# Sheet2.net
KiCad netlist of a schematic drawn in Altium Designer
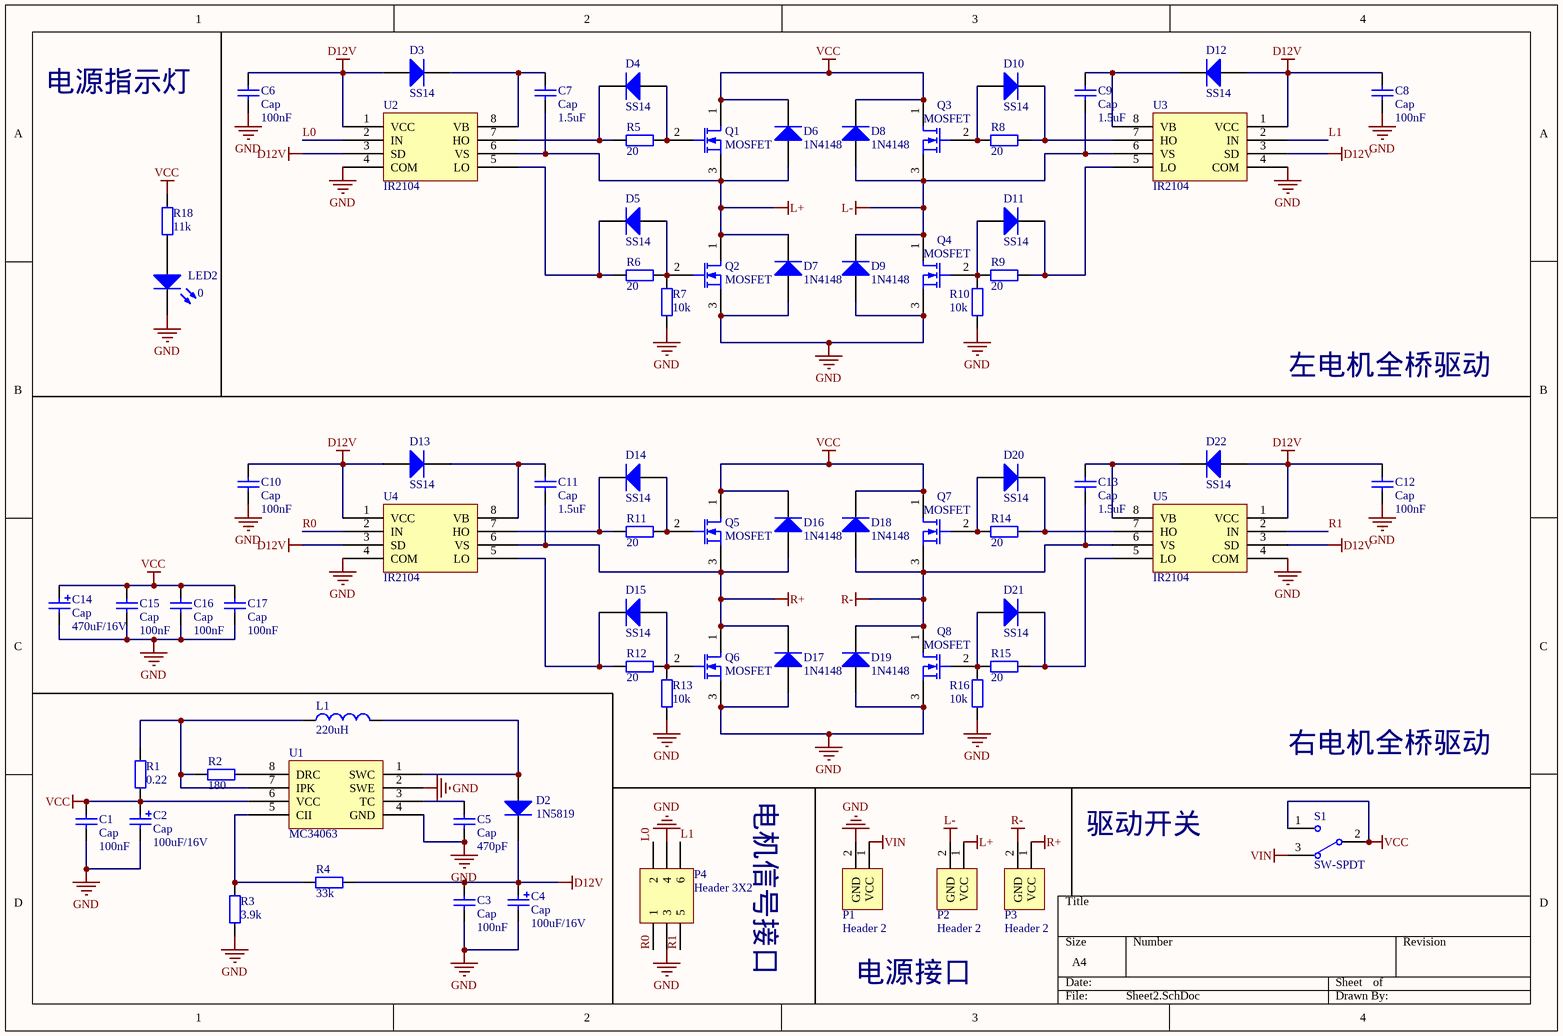
[diagram p0: Sheet2.SchDoc]

(export (version "E")
  (design (tool "Eeschema 10.0.6"))
  (components
    (comp (ref "C1")
      (value "Cap")
      (footprint "0603C")
      (description "Capacitor")
      (fields (field (name "ALTIUM_VALUE") "100nF") (field (name "PUBLISHER") "Altium Limited"))
      (libsource (lib "Schlib1") (part "Cap"))
    )
    (comp (ref "C2")
      (value "Cap")
      (footprint "电解电容")
      (description "Capacitor")
      (fields (field (name "ALTIUM_VALUE") "100uF/16V") (field (name "PUBLISHER") "Altium Limited"))
      (libsource (lib "Schlib1") (part "Cap2"))
    )
    (comp (ref "C3")
      (value "Cap")
      (footprint "0603C")
      (description "Capacitor")
      (fields (field (name "ALTIUM_VALUE") "100nF") (field (name "PUBLISHER") "Altium Limited"))
      (libsource (lib "Schlib1") (part "Cap"))
    )
    (comp (ref "C4")
      (value "Cap")
      (footprint "电解电容")
      (description "Capacitor")
      (fields (field (name "ALTIUM_VALUE") "100uF/16V") (field (name "PUBLISHER") "Altium Limited"))
      (libsource (lib "Schlib1") (part "Cap2"))
    )
    (comp (ref "C5")
      (value "Cap")
      (footprint "0603C")
      (description "Capacitor")
      (fields (field (name "ALTIUM_VALUE") "470pF") (field (name "PUBLISHER") "Altium Limited"))
      (libsource (lib "Schlib1") (part "Cap"))
    )
    (comp (ref "C6")
      (value "Cap")
      (footprint "0603C")
      (description "Capacitor")
      (fields (field (name "ALTIUM_VALUE") "100nF") (field (name "PUBLISHER") "Altium Limited"))
      (libsource (lib "Schlib1") (part "Cap"))
    )
    (comp (ref "C7")
      (value "Cap")
      (footprint "0603C")
      (description "Capacitor")
      (fields (field (name "ALTIUM_VALUE") "1.5uF") (field (name "PUBLISHER") "Altium Limited"))
      (libsource (lib "Schlib1") (part "Cap"))
    )
    (comp (ref "C8")
      (value "Cap")
      (footprint "0603C")
      (description "Capacitor")
      (fields (field (name "ALTIUM_VALUE") "100nF") (field (name "PUBLISHER") "Altium Limited"))
      (libsource (lib "Schlib1") (part "Cap"))
    )
    (comp (ref "C9")
      (value "Cap")
      (footprint "0603C")
      (description "Capacitor")
      (fields (field (name "ALTIUM_VALUE") "1.5uF") (field (name "PUBLISHER") "Altium Limited"))
      (libsource (lib "Schlib1") (part "Cap"))
    )
    (comp (ref "C10")
      (value "Cap")
      (footprint "0603C")
      (description "Capacitor")
      (fields (field (name "ALTIUM_VALUE") "100nF") (field (name "PUBLISHER") "Altium Limited"))
      (libsource (lib "Schlib1") (part "Cap"))
    )
    (comp (ref "C11")
      (value "Cap")
      (footprint "0603C")
      (description "Capacitor")
      (fields (field (name "ALTIUM_VALUE") "1.5uF") (field (name "PUBLISHER") "Altium Limited"))
      (libsource (lib "Schlib1") (part "Cap"))
    )
    (comp (ref "C12")
      (value "Cap")
      (footprint "0603C")
      (description "Capacitor")
      (fields (field (name "ALTIUM_VALUE") "100nF") (field (name "PUBLISHER") "Altium Limited"))
      (libsource (lib "Schlib1") (part "Cap"))
    )
    (comp (ref "C13")
      (value "Cap")
      (footprint "0603C")
      (description "Capacitor")
      (fields (field (name "ALTIUM_VALUE") "1.5uF") (field (name "PUBLISHER") "Altium Limited"))
      (libsource (lib "Schlib1") (part "Cap"))
    )
    (comp (ref "C14")
      (value "Cap")
      (footprint "CAP5.08/8")
      (description "Capacitor")
      (fields (field (name "ALTIUM_VALUE") "470uF/16V") (field (name "PUBLISHER") "Altium Limited"))
      (libsource (lib "Schlib1") (part "Cap2"))
    )
    (comp (ref "C15")
      (value "Cap")
      (footprint "0603C")
      (description "Capacitor")
      (fields (field (name "ALTIUM_VALUE") "100nF") (field (name "PUBLISHER") "Altium Limited"))
      (libsource (lib "Schlib1") (part "Cap"))
    )
    (comp (ref "C16")
      (value "Cap")
      (footprint "0603C")
      (description "Capacitor")
      (fields (field (name "ALTIUM_VALUE") "100nF") (field (name "PUBLISHER") "Altium Limited"))
      (libsource (lib "Schlib1") (part "Cap"))
    )
    (comp (ref "C17")
      (value "Cap")
      (footprint "0603C")
      (description "Capacitor")
      (fields (field (name "ALTIUM_VALUE") "100nF") (field (name "PUBLISHER") "Altium Limited"))
      (libsource (lib "Schlib1") (part "Cap"))
    )
    (comp (ref "D2")
      (value "1N5819")
      (footprint "ss54")
      (description "Default Diode")
      (fields (field (name "PUBLISHER") "Altium Limited"))
      (libsource (lib "Schlib1") (part "Diode_1"))
    )
    (comp (ref "D3")
      (value "SS14")
      (footprint "ss54")
      (description "Default Diode")
      (fields (field (name "PUBLISHER") "Altium Limited"))
      (libsource (lib "Schlib1") (part "Diode_1"))
    )
    (comp (ref "D4")
      (value "SS14")
      (footprint "ss54")
      (description "Default Diode")
      (fields (field (name "PUBLISHER") "Altium Limited"))
      (libsource (lib "Schlib1") (part "Diode_1"))
    )
    (comp (ref "D5")
      (value "SS14")
      (footprint "ss54")
      (description "Default Diode")
      (fields (field (name "PUBLISHER") "Altium Limited"))
      (libsource (lib "Schlib1") (part "Diode_1"))
    )
    (comp (ref "D6")
      (value "1N4148")
      (footprint "SOD123")
      (description "Default Diode")
      (fields (field (name "PUBLISHER") "Altium Limited"))
      (libsource (lib "Schlib1") (part "Diode_2"))
    )
    (comp (ref "D7")
      (value "1N4148")
      (footprint "SOD123")
      (description "Default Diode")
      (fields (field (name "PUBLISHER") "Altium Limited"))
      (libsource (lib "Schlib1") (part "Diode_2"))
    )
    (comp (ref "D8")
      (value "1N4148")
      (footprint "SOD123")
      (description "Default Diode")
      (fields (field (name "PUBLISHER") "Altium Limited"))
      (libsource (lib "Schlib1") (part "Diode_2"))
    )
    (comp (ref "D9")
      (value "1N4148")
      (footprint "SOD123")
      (description "Default Diode")
      (fields (field (name "PUBLISHER") "Altium Limited"))
      (libsource (lib "Schlib1") (part "Diode_2"))
    )
    (comp (ref "D10")
      (value "SS14")
      (footprint "ss54")
      (description "Default Diode")
      (fields (field (name "PUBLISHER") "Altium Limited"))
      (libsource (lib "Schlib1") (part "Diode_1"))
    )
    (comp (ref "D11")
      (value "SS14")
      (footprint "ss54")
      (description "Default Diode")
      (fields (field (name "PUBLISHER") "Altium Limited"))
      (libsource (lib "Schlib1") (part "Diode_1"))
    )
    (comp (ref "D12")
      (value "SS14")
      (footprint "ss54")
      (description "Default Diode")
      (fields (field (name "PUBLISHER") "Altium Limited"))
      (libsource (lib "Schlib1") (part "Diode_1"))
    )
    (comp (ref "D13")
      (value "SS14")
      (footprint "ss54")
      (description "Default Diode")
      (fields (field (name "PUBLISHER") "Altium Limited"))
      (libsource (lib "Schlib1") (part "Diode_1"))
    )
    (comp (ref "D14")
      (value "SS14")
      (footprint "ss54")
      (description "Default Diode")
      (fields (field (name "PUBLISHER") "Altium Limited"))
      (libsource (lib "Schlib1") (part "Diode_1"))
    )
    (comp (ref "D15")
      (value "SS14")
      (footprint "ss54")
      (description "Default Diode")
      (fields (field (name "PUBLISHER") "Altium Limited"))
      (libsource (lib "Schlib1") (part "Diode_1"))
    )
    (comp (ref "D16")
      (value "1N4148")
      (footprint "SOD123")
      (description "Default Diode")
      (fields (field (name "PUBLISHER") "Altium Limited"))
      (libsource (lib "Schlib1") (part "Diode_2"))
    )
    (comp (ref "D17")
      (value "1N4148")
      (footprint "SOD123")
      (description "Default Diode")
      (fields (field (name "PUBLISHER") "Altium Limited"))
      (libsource (lib "Schlib1") (part "Diode_2"))
    )
    (comp (ref "D18")
      (value "1N4148")
      (footprint "SOD123")
      (description "Default Diode")
      (fields (field (name "PUBLISHER") "Altium Limited"))
      (libsource (lib "Schlib1") (part "Diode_2"))
    )
    (comp (ref "D19")
      (value "1N4148")
      (footprint "SOD123")
      (description "Default Diode")
      (fields (field (name "PUBLISHER") "Altium Limited"))
      (libsource (lib "Schlib1") (part "Diode_2"))
    )
    (comp (ref "D20")
      (value "SS14")
      (footprint "ss54")
      (description "Default Diode")
      (fields (field (name "PUBLISHER") "Altium Limited"))
      (libsource (lib "Schlib1") (part "Diode_1"))
    )
    (comp (ref "D21")
      (value "SS14")
      (footprint "ss54")
      (description "Default Diode")
      (fields (field (name "PUBLISHER") "Altium Limited"))
      (libsource (lib "Schlib1") (part "Diode_1"))
    )
    (comp (ref "D22")
      (value "SS14")
      (footprint "ss54")
      (description "Default Diode")
      (fields (field (name "PUBLISHER") "Altium Limited"))
      (libsource (lib "Schlib1") (part "Diode_1"))
    )
    (comp (ref "L1")
      (value "220uH")
      (footprint "cd54")
      (description "Inductor")
      (fields (field (name "PUBLISHER") "Altium Limited"))
      (libsource (lib "Schlib1") (part "Inductor_2"))
    )
    (comp (ref "LED2")
      (value "0")
      (footprint "0603C")
      (description "Typical RED, GREEN, YELLOW, AMBER GaAs LED")
      (fields (field (name "PUBLISHER") "Altium Limited"))
      (libsource (lib "Schlib1") (part "LED2"))
    )
    (comp (ref "P1")
      (value "Header 2")
      (footprint "VCCBAT")
      (description "Header, 2-Pin")
      (fields (field (name "PUBLISHER") "Altium Limited"))
      (libsource (lib "Schlib1") (part "Header 2_2"))
    )
    (comp (ref "P2")
      (value "Header 2")
      (footprint "VCCBAT")
      (description "Header, 2-Pin")
      (fields (field (name "PUBLISHER") "Altium Limited"))
      (libsource (lib "Schlib1") (part "Header 2_2"))
    )
    (comp (ref "P3")
      (value "Header 2")
      (footprint "VCCBAT")
      (description "Header, 2-Pin")
      (fields (field (name "PUBLISHER") "Altium Limited"))
      (libsource (lib "Schlib1") (part "Header 2_2"))
    )
    (comp (ref "P4")
      (value "Header 3X2")
      (footprint "HDR2X3")
      (description "Header, 3-Pin, Dual row")
      (fields (field (name "PUBLISHER") "Altium Limited"))
      (libsource (lib "Miscellaneous Connectors") (part "Header 3X2"))
    )
    (comp (ref "Q1") (value "MOSFET") (footprint "DPAK-1") (libsource (lib "Schlib1") (part "MOSFET-N")))
    (comp (ref "Q2") (value "MOSFET") (footprint "DPAK-1") (libsource (lib "Schlib1") (part "MOSFET-N")))
    (comp (ref "Q3") (value "MOSFET") (footprint "DPAK-1") (libsource (lib "Schlib1") (part "MOSFET-N")))
    (comp (ref "Q4") (value "MOSFET") (footprint "DPAK-1") (libsource (lib "Schlib1") (part "MOSFET-N")))
    (comp (ref "Q5") (value "MOSFET") (footprint "DPAK-1") (libsource (lib "Schlib1") (part "MOSFET-N")))
    (comp (ref "Q6") (value "MOSFET") (footprint "DPAK-1") (libsource (lib "Schlib1") (part "MOSFET-N")))
    (comp (ref "Q7") (value "MOSFET") (footprint "DPAK-1") (libsource (lib "Schlib1") (part "MOSFET-N")))
    (comp (ref "Q8") (value "MOSFET") (footprint "DPAK-1") (libsource (lib "Schlib1") (part "MOSFET-N")))
    (comp (ref "R1")
      (value "0.22")
      (footprint "0603R")
      (description "Resistor")
      (fields (field (name "Comment") "Res2") (field (name "PUBLISHER") "Altium Limited"))
      (libsource (lib "") (part "Res2_1"))
    )
    (comp (ref "R2")
      (value "180")
      (footprint "0603R")
      (description "Resistor")
      (fields (field (name "Comment") "Res2") (field (name "PUBLISHER") "Altium Limited"))
      (libsource (lib "") (part "Res2_2"))
    )
    (comp (ref "R3")
      (value "3.9k")
      (footprint "0603R")
      (description "Resistor")
      (fields (field (name "Comment") "Res2") (field (name "PUBLISHER") "Altium Limited"))
      (libsource (lib "Schlib1") (part "Res2"))
    )
    (comp (ref "R4")
      (value "33k")
      (footprint "0603R")
      (description "Resistor")
      (fields (field (name "Comment") "Res2") (field (name "PUBLISHER") "Altium Limited"))
      (libsource (lib "") (part "Res2_2"))
    )
    (comp (ref "R5")
      (value "20")
      (footprint "0603R")
      (description "Resistor 用了15欧")
      (fields (field (name "Comment") "Res2") (field (name "PUBLISHER") "Altium Limited"))
      (libsource (lib "") (part "Res2_2"))
    )
    (comp (ref "R6")
      (value "20")
      (footprint "0603R")
      (description "Resistor")
      (fields (field (name "Comment") "Res2") (field (name "PUBLISHER") "Altium Limited"))
      (libsource (lib "") (part "Res2_2"))
    )
    (comp (ref "R7")
      (value "10k")
      (footprint "0603R")
      (description "Resistor")
      (fields (field (name "Comment") "Res2") (field (name "PUBLISHER") "Altium Limited"))
      (libsource (lib "") (part "Res2_1"))
    )
    (comp (ref "R8")
      (value "20")
      (footprint "0603R")
      (description "Resistor")
      (fields (field (name "Comment") "Res2") (field (name "PUBLISHER") "Altium Limited"))
      (libsource (lib "") (part "Res2_1"))
    )
    (comp (ref "R9")
      (value "20")
      (footprint "0603R")
      (description "Resistor")
      (fields (field (name "Comment") "Res2") (field (name "PUBLISHER") "Altium Limited"))
      (libsource (lib "") (part "Res2_1"))
    )
    (comp (ref "R10")
      (value "10k")
      (footprint "0603R")
      (description "Resistor")
      (fields (field (name "Comment") "Res2") (field (name "PUBLISHER") "Altium Limited"))
      (libsource (lib "") (part "Res2_3"))
    )
    (comp (ref "R11")
      (value "20")
      (footprint "0603R")
      (description "Resistor")
      (fields (field (name "Comment") "Res2") (field (name "PUBLISHER") "Altium Limited"))
      (libsource (lib "") (part "Res2_2"))
    )
    (comp (ref "R12")
      (value "20")
      (footprint "0603R")
      (description "Resistor")
      (fields (field (name "Comment") "Res2") (field (name "PUBLISHER") "Altium Limited"))
      (libsource (lib "") (part "Res2_2"))
    )
    (comp (ref "R13")
      (value "10k")
      (footprint "0603R")
      (description "Resistor")
      (fields (field (name "Comment") "Res2") (field (name "PUBLISHER") "Altium Limited"))
      (libsource (lib "") (part "Res2_1"))
    )
    (comp (ref "R14")
      (value "20")
      (footprint "0603R")
      (description "Resistor")
      (fields (field (name "Comment") "Res2") (field (name "PUBLISHER") "Altium Limited"))
      (libsource (lib "") (part "Res2_1"))
    )
    (comp (ref "R15")
      (value "20")
      (footprint "0603R")
      (description "Resistor")
      (fields (field (name "Comment") "Res2") (field (name "PUBLISHER") "Altium Limited"))
      (libsource (lib "") (part "Res2_1"))
    )
    (comp (ref "R16")
      (value "10k")
      (footprint "0603R")
      (description "Resistor")
      (fields (field (name "Comment") "Res2") (field (name "PUBLISHER") "Altium Limited"))
      (libsource (lib "") (part "Res2_3"))
    )
    (comp (ref "R18")
      (value "11k")
      (footprint "0603R")
      (description "Resistor")
      (fields (field (name "Comment") "Res2") (field (name "PUBLISHER") "Altium Limited"))
      (libsource (lib "") (part "Res2_1"))
    )
    (comp (ref "S1")
      (value "SW-SPDT")
      (footprint "SW")
      (description "SPDT Subminiature Toggle Switch, Right Angle Mounting, Vertical Actuation")
      (fields (field (name "PUBLISHER") "Altium Limited"))
      (libsource (lib "Miscellaneous Devices") (part "SW-SPDT"))
    )
    (comp (ref "U1") (value "MC34063") (footprint "SOIC-8") (libsource (lib "Schlib1") (part "MC34063")))
    (comp (ref "U2") (value "IR2104") (footprint "SOIC-8") (libsource (lib "") (part "IR2104_1")))
    (comp (ref "U3") (value "IR2104") (footprint "SOIC-8") (libsource (lib "Schlib1") (part "IR2104")))
    (comp (ref "U4") (value "IR2104") (footprint "SOIC-8") (libsource (lib "") (part "IR2104_1")))
    (comp (ref "U5") (value "IR2104") (footprint "SOIC-8") (libsource (lib "Schlib1") (part "IR2104")))
  )
  (nets
    (net (code "1") (name "/L0") (class "Default")
      (node (ref "P4") (pin "2") (pinfunction "2_2") (pintype "passive"))
      (node (ref "U2") (pin "2") (pinfunction "IN_2") (pintype "passive"))
    )
    (net (code "2") (name "/L1") (class "Default")
      (node (ref "P4") (pin "6") (pinfunction "6_6") (pintype "passive"))
      (node (ref "U3") (pin "2") (pinfunction "IN_2") (pintype "passive"))
    )
    (net (code "3") (name "/R0") (class "Default")
      (node (ref "P4") (pin "1") (pinfunction "1_1") (pintype "passive"))
      (node (ref "U4") (pin "2") (pinfunction "IN_2") (pintype "passive"))
    )
    (net (code "4") (name "/R1") (class "Default")
      (node (ref "P4") (pin "5") (pinfunction "5_5") (pintype "passive"))
      (node (ref "U5") (pin "2") (pinfunction "IN_2") (pintype "passive"))
    )
    (net (code "5") (name "D12V") (class "Default")
      (node (ref "C10") (pin "2") (pinfunction "2_2") (pintype "passive"))
      (node (ref "C12") (pin "2") (pinfunction "2_2") (pintype "passive"))
      (node (ref "C3") (pin "2") (pinfunction "2_2") (pintype "passive"))
      (node (ref "C4") (pin "1") (pinfunction "1_1") (pintype "passive"))
      (node (ref "C6") (pin "2") (pinfunction "2_2") (pintype "passive"))
      (node (ref "C8") (pin "2") (pinfunction "2_2") (pintype "passive"))
      (node (ref "D12") (pin "1") (pinfunction "A_1") (pintype "passive"))
      (node (ref "D13") (pin "1") (pinfunction "A_1") (pintype "passive"))
      (node (ref "D2") (pin "2") (pinfunction "K_2") (pintype "passive"))
      (node (ref "D22") (pin "1") (pinfunction "A_1") (pintype "passive"))
      (node (ref "D3") (pin "1") (pinfunction "A_1") (pintype "passive"))
      (node (ref "R4") (pin "1") (pinfunction "1_1") (pintype "passive"))
      (node (ref "U2") (pin "1") (pinfunction "VCC_1") (pintype "passive"))
      (node (ref "U2") (pin "3") (pinfunction "SD_3") (pintype "passive"))
      (node (ref "U3") (pin "1") (pinfunction "VCC_1") (pintype "passive"))
      (node (ref "U3") (pin "3") (pinfunction "SD_3") (pintype "passive"))
      (node (ref "U4") (pin "1") (pinfunction "VCC_1") (pintype "passive"))
      (node (ref "U4") (pin "3") (pinfunction "SD_3") (pintype "passive"))
      (node (ref "U5") (pin "1") (pinfunction "VCC_1") (pintype "passive"))
      (node (ref "U5") (pin "3") (pinfunction "SD_3") (pintype "passive"))
    )
    (net (code "6") (name "GND") (class "Default")
      (node (ref "C1") (pin "1") (pinfunction "1_1") (pintype "passive"))
      (node (ref "C10") (pin "1") (pinfunction "1_1") (pintype "passive"))
      (node (ref "C12") (pin "1") (pinfunction "1_1") (pintype "passive"))
      (node (ref "C14") (pin "2") (pinfunction "2_2") (pintype "passive"))
      (node (ref "C15") (pin "1") (pinfunction "1_1") (pintype "passive"))
      (node (ref "C16") (pin "1") (pinfunction "1_1") (pintype "passive"))
      (node (ref "C17") (pin "1") (pinfunction "1_1") (pintype "passive"))
      (node (ref "C2") (pin "2") (pinfunction "2_2") (pintype "passive"))
      (node (ref "C3") (pin "1") (pinfunction "1_1") (pintype "passive"))
      (node (ref "C4") (pin "2") (pinfunction "2_2") (pintype "passive"))
      (node (ref "C5") (pin "1") (pinfunction "1_1") (pintype "passive"))
      (node (ref "C6") (pin "1") (pinfunction "1_1") (pintype "passive"))
      (node (ref "C8") (pin "1") (pinfunction "1_1") (pintype "passive"))
      (node (ref "D17") (pin "1") (pinfunction "A_1") (pintype "passive"))
      (node (ref "D19") (pin "1") (pinfunction "A_1") (pintype "passive"))
      (node (ref "D7") (pin "1") (pinfunction "A_1") (pintype "passive"))
      (node (ref "D9") (pin "1") (pinfunction "A_1") (pintype "passive"))
      (node (ref "LED2") (pin "2") (pinfunction "K_2") (pintype "passive"))
      (node (ref "P1") (pin "2") (pinfunction "GND_2") (pintype "passive"))
      (node (ref "P4") (pin "3") (pinfunction "3_3") (pintype "passive"))
      (node (ref "P4") (pin "4") (pinfunction "4_4") (pintype "passive"))
      (node (ref "Q2") (pin "3") (pinfunction "3_3") (pintype "passive"))
      (node (ref "Q4") (pin "3") (pinfunction "3_3") (pintype "passive"))
      (node (ref "Q6") (pin "3") (pinfunction "3_3") (pintype "passive"))
      (node (ref "Q8") (pin "3") (pinfunction "3_3") (pintype "passive"))
      (node (ref "R10") (pin "1") (pinfunction "1_1") (pintype "passive"))
      (node (ref "R13") (pin "1") (pinfunction "1_1") (pintype "passive"))
      (node (ref "R16") (pin "1") (pinfunction "1_1") (pintype "passive"))
      (node (ref "R3") (pin "2") (pinfunction "2_2") (pintype "passive"))
      (node (ref "R7") (pin "1") (pinfunction "1_1") (pintype "passive"))
      (node (ref "U1") (pin "2") (pinfunction "SWE_2") (pintype "passive"))
      (node (ref "U1") (pin "4") (pinfunction "GND_4") (pintype "passive"))
      (node (ref "U2") (pin "4") (pinfunction "COM_4") (pintype "passive"))
      (node (ref "U3") (pin "4") (pinfunction "COM_4") (pintype "passive"))
      (node (ref "U4") (pin "4") (pinfunction "COM_4") (pintype "passive"))
      (node (ref "U5") (pin "4") (pinfunction "COM_4") (pintype "passive"))
    )
    (net (code "7") (name "L+") (class "Default")
      (node (ref "C7") (pin "1") (pinfunction "1_1") (pintype "passive"))
      (node (ref "D6") (pin "1") (pinfunction "A_1") (pintype "passive"))
      (node (ref "D7") (pin "2") (pinfunction "K_2") (pintype "passive"))
      (node (ref "P2") (pin "1") (pinfunction "VCC_1") (pintype "passive"))
      (node (ref "Q1") (pin "3") (pinfunction "3_3") (pintype "passive"))
      (node (ref "Q2") (pin "1") (pinfunction "D_1") (pintype "passive"))
      (node (ref "U2") (pin "6") (pinfunction "VS_6") (pintype "passive"))
    )
    (net (code "8") (name "L-") (class "Default")
      (node (ref "C9") (pin "1") (pinfunction "1_1") (pintype "passive"))
      (node (ref "D8") (pin "1") (pinfunction "A_1") (pintype "passive"))
      (node (ref "D9") (pin "2") (pinfunction "K_2") (pintype "passive"))
      (node (ref "P2") (pin "2") (pinfunction "GND_2") (pintype "passive"))
      (node (ref "Q3") (pin "3") (pinfunction "3_3") (pintype "passive"))
      (node (ref "Q4") (pin "1") (pinfunction "D_1") (pintype "passive"))
      (node (ref "U3") (pin "6") (pinfunction "VS_6") (pintype "passive"))
    )
    (net (code "9") (name "Net-(D2-A)") (class "Default")
      (node (ref "D2") (pin "1") (pinfunction "A_1") (pintype "passive"))
      (node (ref "L1") (pin "2") (pinfunction "2_2") (pintype "passive"))
      (node (ref "U1") (pin "1") (pinfunction "SWC_1") (pintype "passive"))
    )
    (net (code "10") (name "Net-(D3-K)") (class "Default")
      (node (ref "C7") (pin "2") (pinfunction "2_2") (pintype "passive"))
      (node (ref "D3") (pin "2") (pinfunction "K_2") (pintype "passive"))
      (node (ref "U2") (pin "8") (pinfunction "VB_8") (pintype "passive"))
    )
    (net (code "11") (name "Net-(D4-A)") (class "Default")
      (node (ref "D4") (pin "1") (pinfunction "A_1") (pintype "passive"))
      (node (ref "Q1") (pin "2") (pinfunction "G_2") (pintype "passive"))
      (node (ref "R5") (pin "1") (pinfunction "1_1") (pintype "passive"))
    )
    (net (code "12") (name "Net-(D4-K)") (class "Default")
      (node (ref "D4") (pin "2") (pinfunction "K_2") (pintype "passive"))
      (node (ref "R5") (pin "2") (pinfunction "2_2") (pintype "passive"))
      (node (ref "U2") (pin "7") (pinfunction "HO_7") (pintype "passive"))
    )
    (net (code "13") (name "Net-(D5-A)") (class "Default")
      (node (ref "D5") (pin "1") (pinfunction "A_1") (pintype "passive"))
      (node (ref "Q2") (pin "2") (pinfunction "G_2") (pintype "passive"))
      (node (ref "R6") (pin "1") (pinfunction "1_1") (pintype "passive"))
      (node (ref "R7") (pin "2") (pinfunction "2_2") (pintype "passive"))
    )
    (net (code "14") (name "Net-(D5-K)") (class "Default")
      (node (ref "D5") (pin "2") (pinfunction "K_2") (pintype "passive"))
      (node (ref "R6") (pin "2") (pinfunction "2_2") (pintype "passive"))
      (node (ref "U2") (pin "5") (pinfunction "LO_5") (pintype "passive"))
    )
    (net (code "15") (name "Net-(D10-A)") (class "Default")
      (node (ref "D10") (pin "1") (pinfunction "A_1") (pintype "passive"))
      (node (ref "Q3") (pin "2") (pinfunction "G_2") (pintype "passive"))
      (node (ref "R8") (pin "1") (pinfunction "1_1") (pintype "passive"))
    )
    (net (code "16") (name "Net-(D10-K)") (class "Default")
      (node (ref "D10") (pin "2") (pinfunction "K_2") (pintype "passive"))
      (node (ref "R8") (pin "2") (pinfunction "2_2") (pintype "passive"))
      (node (ref "U3") (pin "7") (pinfunction "HO_7") (pintype "passive"))
    )
    (net (code "17") (name "Net-(D11-A)") (class "Default")
      (node (ref "D11") (pin "1") (pinfunction "A_1") (pintype "passive"))
      (node (ref "Q4") (pin "2") (pinfunction "G_2") (pintype "passive"))
      (node (ref "R10") (pin "2") (pinfunction "2_2") (pintype "passive"))
      (node (ref "R9") (pin "1") (pinfunction "1_1") (pintype "passive"))
    )
    (net (code "18") (name "Net-(D11-K)") (class "Default")
      (node (ref "D11") (pin "2") (pinfunction "K_2") (pintype "passive"))
      (node (ref "R9") (pin "2") (pinfunction "2_2") (pintype "passive"))
      (node (ref "U3") (pin "5") (pinfunction "LO_5") (pintype "passive"))
    )
    (net (code "19") (name "Net-(D12-K)") (class "Default")
      (node (ref "C9") (pin "2") (pinfunction "2_2") (pintype "passive"))
      (node (ref "D12") (pin "2") (pinfunction "K_2") (pintype "passive"))
      (node (ref "U3") (pin "8") (pinfunction "VB_8") (pintype "passive"))
    )
    (net (code "20") (name "Net-(D13-K)") (class "Default")
      (node (ref "C11") (pin "2") (pinfunction "2_2") (pintype "passive"))
      (node (ref "D13") (pin "2") (pinfunction "K_2") (pintype "passive"))
      (node (ref "U4") (pin "8") (pinfunction "VB_8") (pintype "passive"))
    )
    (net (code "21") (name "Net-(D14-A)") (class "Default")
      (node (ref "D14") (pin "1") (pinfunction "A_1") (pintype "passive"))
      (node (ref "Q5") (pin "2") (pinfunction "G_2") (pintype "passive"))
      (node (ref "R11") (pin "1") (pinfunction "1_1") (pintype "passive"))
    )
    (net (code "22") (name "Net-(D14-K)") (class "Default")
      (node (ref "D14") (pin "2") (pinfunction "K_2") (pintype "passive"))
      (node (ref "R11") (pin "2") (pinfunction "2_2") (pintype "passive"))
      (node (ref "U4") (pin "7") (pinfunction "HO_7") (pintype "passive"))
    )
    (net (code "23") (name "Net-(D15-A)") (class "Default")
      (node (ref "D15") (pin "1") (pinfunction "A_1") (pintype "passive"))
      (node (ref "Q6") (pin "2") (pinfunction "G_2") (pintype "passive"))
      (node (ref "R12") (pin "1") (pinfunction "1_1") (pintype "passive"))
      (node (ref "R13") (pin "2") (pinfunction "2_2") (pintype "passive"))
    )
    (net (code "24") (name "Net-(D15-K)") (class "Default")
      (node (ref "D15") (pin "2") (pinfunction "K_2") (pintype "passive"))
      (node (ref "R12") (pin "2") (pinfunction "2_2") (pintype "passive"))
      (node (ref "U4") (pin "5") (pinfunction "LO_5") (pintype "passive"))
    )
    (net (code "25") (name "Net-(D20-A)") (class "Default")
      (node (ref "D20") (pin "1") (pinfunction "A_1") (pintype "passive"))
      (node (ref "Q7") (pin "2") (pinfunction "G_2") (pintype "passive"))
      (node (ref "R14") (pin "1") (pinfunction "1_1") (pintype "passive"))
    )
    (net (code "26") (name "Net-(D20-K)") (class "Default")
      (node (ref "D20") (pin "2") (pinfunction "K_2") (pintype "passive"))
      (node (ref "R14") (pin "2") (pinfunction "2_2") (pintype "passive"))
      (node (ref "U5") (pin "7") (pinfunction "HO_7") (pintype "passive"))
    )
    (net (code "27") (name "Net-(D21-A)") (class "Default")
      (node (ref "D21") (pin "1") (pinfunction "A_1") (pintype "passive"))
      (node (ref "Q8") (pin "2") (pinfunction "G_2") (pintype "passive"))
      (node (ref "R15") (pin "1") (pinfunction "1_1") (pintype "passive"))
      (node (ref "R16") (pin "2") (pinfunction "2_2") (pintype "passive"))
    )
    (net (code "28") (name "Net-(D21-K)") (class "Default")
      (node (ref "D21") (pin "2") (pinfunction "K_2") (pintype "passive"))
      (node (ref "R15") (pin "2") (pinfunction "2_2") (pintype "passive"))
      (node (ref "U5") (pin "5") (pinfunction "LO_5") (pintype "passive"))
    )
    (net (code "29") (name "Net-(D22-K)") (class "Default")
      (node (ref "C13") (pin "2") (pinfunction "2_2") (pintype "passive"))
      (node (ref "D22") (pin "2") (pinfunction "K_2") (pintype "passive"))
      (node (ref "U5") (pin "8") (pinfunction "VB_8") (pintype "passive"))
    )
    (net (code "30") (name "Net-(LED2-A)") (class "Default")
      (node (ref "LED2") (pin "1") (pinfunction "A_1") (pintype "passive"))
      (node (ref "R18") (pin "1") (pinfunction "1_1") (pintype "passive"))
    )
    (net (code "31") (name "Net-(U1-CII)") (class "Default")
      (node (ref "R3") (pin "1") (pinfunction "1_1") (pintype "passive"))
      (node (ref "R4") (pin "2") (pinfunction "2_2") (pintype "passive"))
      (node (ref "U1") (pin "5") (pinfunction "CII_5") (pintype "passive"))
    )
    (net (code "32") (name "Net-(U1-DRC)") (class "Default")
      (node (ref "R2") (pin "1") (pinfunction "1_1") (pintype "passive"))
      (node (ref "U1") (pin "8") (pinfunction "DRC_8") (pintype "passive"))
    )
    (net (code "33") (name "Net-(U1-IPK)") (class "Default")
      (node (ref "L1") (pin "1") (pinfunction "1_1") (pintype "passive"))
      (node (ref "R1") (pin "2") (pinfunction "2_2") (pintype "passive"))
      (node (ref "R2") (pin "2") (pinfunction "2_2") (pintype "passive"))
      (node (ref "U1") (pin "7") (pinfunction "IPK_7") (pintype "passive"))
    )
    (net (code "34") (name "Net-(U1-TC)") (class "Default")
      (node (ref "C5") (pin "2") (pinfunction "2_2") (pintype "passive"))
      (node (ref "U1") (pin "3") (pinfunction "TC_3") (pintype "passive"))
    )
    (net (code "35") (name "R+") (class "Default")
      (node (ref "C11") (pin "1") (pinfunction "1_1") (pintype "passive"))
      (node (ref "D16") (pin "1") (pinfunction "A_1") (pintype "passive"))
      (node (ref "D17") (pin "2") (pinfunction "K_2") (pintype "passive"))
      (node (ref "P3") (pin "1") (pinfunction "VCC_1") (pintype "passive"))
      (node (ref "Q5") (pin "3") (pinfunction "3_3") (pintype "passive"))
      (node (ref "Q6") (pin "1") (pinfunction "D_1") (pintype "passive"))
      (node (ref "U4") (pin "6") (pinfunction "VS_6") (pintype "passive"))
    )
    (net (code "36") (name "R-") (class "Default")
      (node (ref "C13") (pin "1") (pinfunction "1_1") (pintype "passive"))
      (node (ref "D18") (pin "1") (pinfunction "A_1") (pintype "passive"))
      (node (ref "D19") (pin "2") (pinfunction "K_2") (pintype "passive"))
      (node (ref "P3") (pin "2") (pinfunction "GND_2") (pintype "passive"))
      (node (ref "Q7") (pin "3") (pinfunction "3_3") (pintype "passive"))
      (node (ref "Q8") (pin "1") (pinfunction "D_1") (pintype "passive"))
      (node (ref "U5") (pin "6") (pinfunction "VS_6") (pintype "passive"))
    )
    (net (code "37") (name "VCC") (class "Default")
      (node (ref "C1") (pin "2") (pinfunction "2_2") (pintype "passive"))
      (node (ref "C14") (pin "1") (pinfunction "1_1") (pintype "passive"))
      (node (ref "C15") (pin "2") (pinfunction "2_2") (pintype "passive"))
      (node (ref "C16") (pin "2") (pinfunction "2_2") (pintype "passive"))
      (node (ref "C17") (pin "2") (pinfunction "2_2") (pintype "passive"))
      (node (ref "C2") (pin "1") (pinfunction "1_1") (pintype "passive"))
      (node (ref "D16") (pin "2") (pinfunction "K_2") (pintype "passive"))
      (node (ref "D18") (pin "2") (pinfunction "K_2") (pintype "passive"))
      (node (ref "D6") (pin "2") (pinfunction "K_2") (pintype "passive"))
      (node (ref "D8") (pin "2") (pinfunction "K_2") (pintype "passive"))
      (node (ref "Q1") (pin "1") (pinfunction "D_1") (pintype "passive"))
      (node (ref "Q3") (pin "1") (pinfunction "D_1") (pintype "passive"))
      (node (ref "Q5") (pin "1") (pinfunction "D_1") (pintype "passive"))
      (node (ref "Q7") (pin "1") (pinfunction "D_1") (pintype "passive"))
      (node (ref "R1") (pin "1") (pinfunction "1_1") (pintype "passive"))
      (node (ref "R18") (pin "2") (pinfunction "2_2") (pintype "passive"))
      (node (ref "S1") (pin "1") (pinfunction "1_1") (pintype "passive"))
      (node (ref "S1") (pin "2") (pinfunction "2_2") (pintype "passive"))
      (node (ref "U1") (pin "6") (pinfunction "VCC_6") (pintype "passive"))
    )
    (net (code "38") (name "VIN") (class "Default")
      (node (ref "P1") (pin "1") (pinfunction "VCC_1") (pintype "passive"))
      (node (ref "S1") (pin "3") (pinfunction "3_3") (pintype "passive"))
    )
  )
)
